# sch.net
KiCad netlist of a schematic drawn in Altium Designer
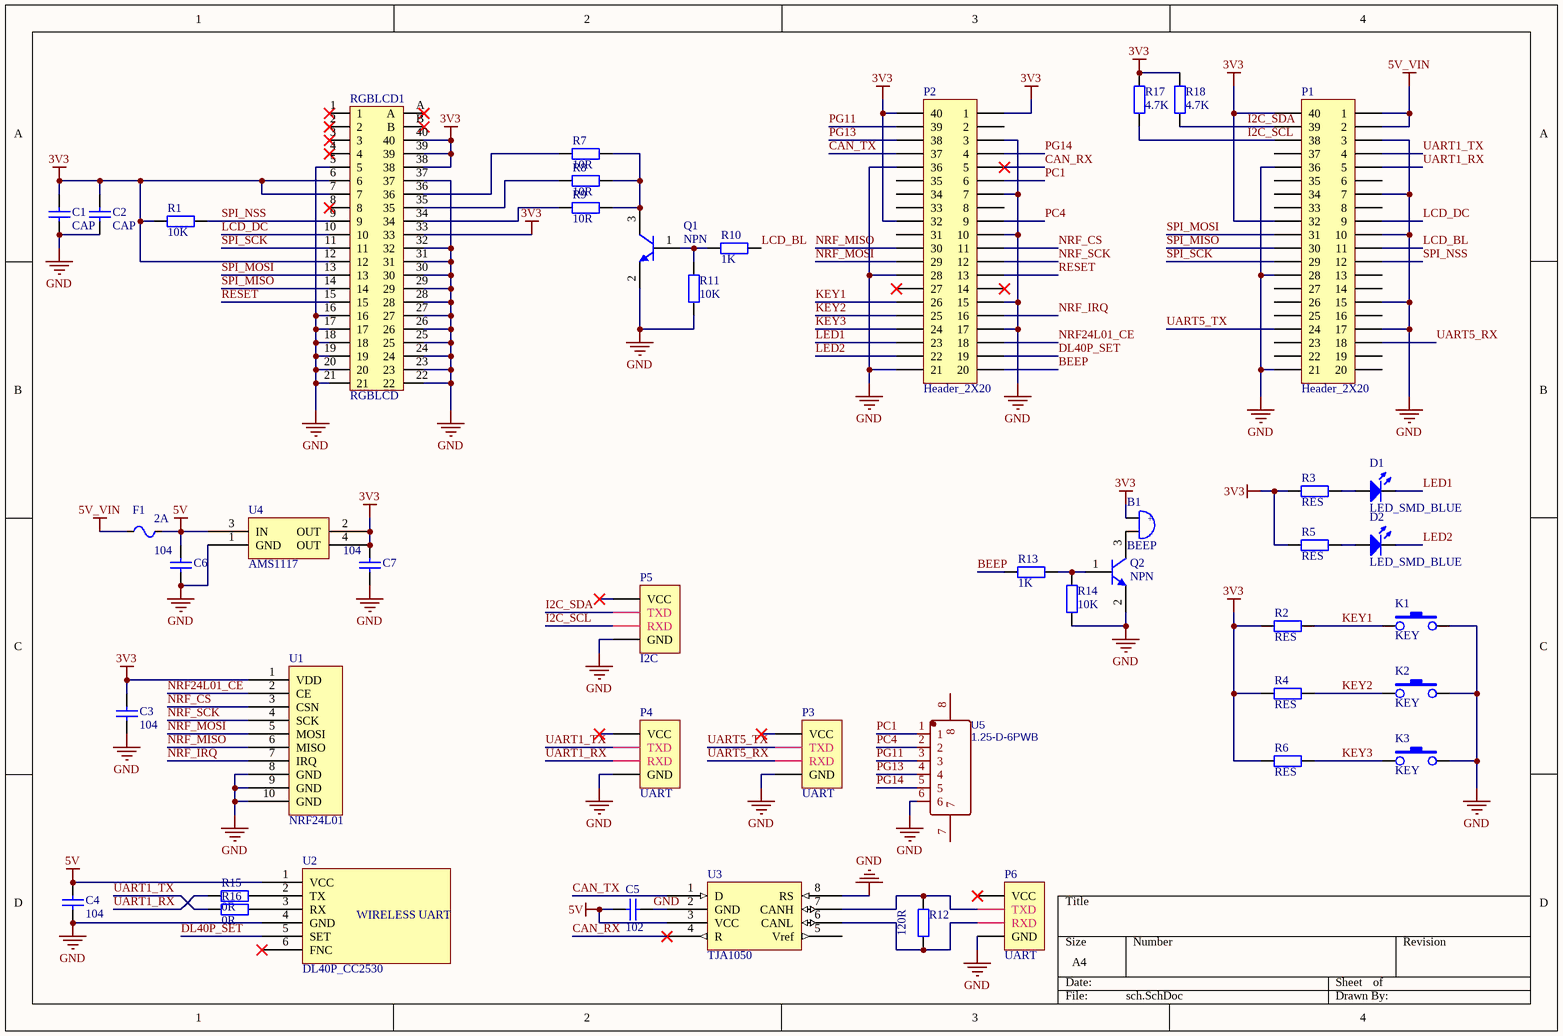
[diagram p0: sch.SchDoc]

(export (version "E")
  (design (tool "Eeschema 10.0.6"))
  (components
    (comp (ref "B1")
      (value "BEEP")
      (footprint "BEEP 5x9x5.5")
      (description "蜂鸣器")
      (libsource (lib "Miscellaneous Model") (part "BEEP"))
    )
    (comp (ref "C1")
      (value "CAP")
      (footprint "Cap-0603")
      (description "贴片陶瓷电容")
      (libsource (lib "Miscellaneous Base") (part "CAP"))
    )
    (comp (ref "C2")
      (value "CAP")
      (footprint "Cap-0603")
      (description "贴片陶瓷电容")
      (libsource (lib "Miscellaneous Base") (part "CAP"))
    )
    (comp (ref "C3")
      (value "104")
      (footprint "Cap-0603")
      (description "贴片陶瓷电容")
      (libsource (lib "Miscellaneous Base") (part "CAP"))
    )
    (comp (ref "C4")
      (value "104")
      (footprint "Cap-0603")
      (description "贴片陶瓷电容")
      (libsource (lib "Miscellaneous Base") (part "CAP"))
    )
    (comp (ref "C5")
      (value "102")
      (footprint "Cap-0603")
      (description "贴片陶瓷电容")
      (libsource (lib "Miscellaneous Base") (part "CAP"))
    )
    (comp (ref "C6")
      (value "104")
      (footprint "Cap-0603")
      (description "贴片陶瓷电容")
      (libsource (lib "Miscellaneous Base") (part "CAP"))
    )
    (comp (ref "C7")
      (value "104")
      (footprint "Cap-0603")
      (description "贴片陶瓷电容")
      (libsource (lib "Miscellaneous Base") (part "CAP"))
    )
    (comp (ref "D1")
      (value "LED_SMD_BLUE")
      (footprint "LED_0603_B")
      (description "发光二极管")
      (libsource (lib "Miscellaneous Transistor") (part "LED_SMD_BLUE"))
    )
    (comp (ref "D2")
      (value "LED_SMD_BLUE")
      (footprint "LED_0603_B")
      (description "发光二极管")
      (libsource (lib "Miscellaneous Transistor") (part "LED_SMD_BLUE"))
    )
    (comp (ref "F1")
      (value "2A")
      (footprint "FU 1206")
      (description "贴片保险丝")
      (fields (field (name "版权归属") "源创客"))
      (libsource (lib "IMX6UL_ALPHA(底板)_V2.0") (part "FU"))
    )
    (comp (ref "K1")
      (value "KEY")
      (footprint "SW-SMD-2X4")
      (libsource (lib "Miscellaneous Switch") (part "KEY"))
    )
    (comp (ref "K2")
      (value "KEY")
      (footprint "SW-SMD-2X4")
      (libsource (lib "Miscellaneous Switch") (part "KEY"))
    )
    (comp (ref "K3")
      (value "KEY")
      (footprint "SW-SMD-2X4")
      (libsource (lib "Miscellaneous Switch") (part "KEY"))
    )
    (comp (ref "P1")
      (value "Header_2X20")
      (footprint "Header 2.54_2X20")
      (libsource (lib "Miscellaneous Header") (part "Header_2X20"))
    )
    (comp (ref "P2")
      (value "Header_2X20")
      (footprint "Header 2.54_2X20")
      (libsource (lib "Miscellaneous Header") (part "Header_2X20"))
    )
    (comp (ref "P3")
      (value "UART")
      (footprint "SMT1.25_4P-90")
      (fields (field (name "PUBLISHER") "Altium Limited"))
      (libsource (lib "我的原理图库") (part "UART port"))
    )
    (comp (ref "P4")
      (value "UART")
      (footprint "SMT1.25_4P-90")
      (fields (field (name "PUBLISHER") "Altium Limited"))
      (libsource (lib "我的原理图库") (part "UART port"))
    )
    (comp (ref "P5")
      (value "I2C")
      (footprint "SMT1.25_4P-90")
      (fields (field (name "PUBLISHER") "Altium Limited"))
      (libsource (lib "我的原理图库") (part "UART port"))
    )
    (comp (ref "P6")
      (value "UART")
      (footprint "SMT1.25_4P-90")
      (fields (field (name "PUBLISHER") "Altium Limited"))
      (libsource (lib "我的原理图库") (part "UART port"))
    )
    (comp (ref "Q1")
      (value "NPN")
      (footprint "SOT23-3")
      (description "贴片三极管")
      (fields (field (name "PUBLISHER") "Altium Limited"))
      (libsource (lib "Miscellaneous Transistor") (part "NPN1"))
    )
    (comp (ref "Q2")
      (value "NPN")
      (footprint "SOT23-3")
      (description "贴片三极管")
      (fields (field (name "PUBLISHER") "Altium Limited"))
      (libsource (lib "Miscellaneous Transistor") (part "NPN1"))
    )
    (comp (ref "R1")
      (value "10K")
      (footprint "Res-0603")
      (description "贴片电阻")
      (libsource (lib "") (part "RES_2"))
    )
    (comp (ref "R2")
      (value "RES")
      (footprint "Res-0603")
      (description "贴片电阻")
      (libsource (lib "") (part "RES_2"))
    )
    (comp (ref "R3")
      (value "RES")
      (footprint "Res-0603")
      (description "贴片电阻")
      (libsource (lib "") (part "RES_2"))
    )
    (comp (ref "R4")
      (value "RES")
      (footprint "Res-0603")
      (description "贴片电阻")
      (libsource (lib "") (part "RES_2"))
    )
    (comp (ref "R5")
      (value "RES")
      (footprint "Res-0603")
      (description "贴片电阻")
      (libsource (lib "") (part "RES_2"))
    )
    (comp (ref "R6")
      (value "RES")
      (footprint "Res-0603")
      (description "贴片电阻")
      (libsource (lib "") (part "RES_2"))
    )
    (comp (ref "R7")
      (value "10R")
      (footprint "Res-0603")
      (description "贴片电阻")
      (libsource (lib "") (part "RES_1"))
    )
    (comp (ref "R8")
      (value "10R")
      (footprint "Res-0603")
      (description "贴片电阻")
      (libsource (lib "") (part "RES_1"))
    )
    (comp (ref "R9")
      (value "10R")
      (footprint "Res-0603")
      (description "贴片电阻")
      (libsource (lib "") (part "RES_1"))
    )
    (comp (ref "R10")
      (value "1K")
      (footprint "Res-0603")
      (description "贴片电阻")
      (libsource (lib "") (part "RES_1"))
    )
    (comp (ref "R11")
      (value "10K")
      (footprint "Res-0603")
      (description "贴片电阻")
      (libsource (lib "") (part "RES_2"))
    )
    (comp (ref "R12")
      (value "120R")
      (footprint "Res-0603")
      (description "贴片电阻")
      (libsource (lib "Miscellaneous Base") (part "RES"))
    )
    (comp (ref "R13")
      (value "1K")
      (footprint "Res-0603")
      (description "贴片电阻")
      (libsource (lib "") (part "RES_1"))
    )
    (comp (ref "R14")
      (value "10K")
      (footprint "Res-0603")
      (description "贴片电阻")
      (libsource (lib "") (part "RES_2"))
    )
    (comp (ref "R15")
      (value "0R")
      (footprint "Res-0603")
      (description "贴片电阻")
      (libsource (lib "") (part "RES_3"))
    )
    (comp (ref "R16")
      (value "0R")
      (footprint "Res-0603")
      (description "贴片电阻")
      (libsource (lib "") (part "RES_3"))
    )
    (comp (ref "R17")
      (value "4.7K")
      (footprint "Res-0603")
      (description "贴片电阻")
      (libsource (lib "Miscellaneous Base") (part "RES"))
    )
    (comp (ref "R18")
      (value "4.7K")
      (footprint "Res-0603")
      (description "贴片电阻")
      (libsource (lib "Miscellaneous Base") (part "RES"))
    )
    (comp (ref "RGBLCD1")
      (value "RGBLCD")
      (footprint "FPC0.5-TOP40P")
      (description "FPC-40P-0.5mm")
      (libsource (lib "IMX6UL_ALPHA(底板)_V2.0") (part "FPC-40"))
    )
    (comp (ref "U1")
      (value "NRF24L01")
      (footprint "PE01-ML01SP4")
      (libsource (lib "OUR_LIB") (part "NRF24L01"))
    )
    (comp (ref "U2")
      (value "DL40P_CC2530")
      (footprint "DL43P_CC2530")
      (libsource (lib "OUR_LIB") (part "DL40P_CC2530"))
    )
    (comp (ref "U3")
      (value "TJA1050")
      (footprint "SOP8_N")
      (libsource (lib "IMX6UL_ALPHA(底板)_V2.0") (part "SN65HVD230D"))
    )
    (comp (ref "U4")
      (value "AMS1117")
      (footprint "AMS1117")
      (libsource (lib "Miscellaneous PMIC") (part "AMS1117"))
    )
    (comp (ref "U5")
      (value "1.25-D-6PWB")
      (footprint "SMT1.25_6P-90")
      (fields (field (name "BOM_SUPPLIER PART") "C35040") (field (name "CONTRIBUTOR") "LCSC"))
      (libsource (lib "我的原理图库") (part "1.25-D-6PWB"))
    )
  )
  (nets
    (net (code "1") (name "/BEEP") (class "Default")
      (node (ref "P2") (pin "20") (pinfunction "20_20") (pintype "power_in"))
      (node (ref "R13") (pin "2") (pinfunction "2_2") (pintype "passive"))
    )
    (net (code "2") (name "/CAN_RX") (class "Default")
      (node (ref "P2") (pin "5") (pinfunction "5_5") (pintype "power_in"))
      (node (ref "U3") (pin "4") (pinfunction "R_4") (pintype "output"))
    )
    (net (code "3") (name "/CAN_TX") (class "Default")
      (node (ref "P2") (pin "37") (pinfunction "37_37") (pintype "power_in"))
      (node (ref "U3") (pin "1") (pinfunction "D_1") (pintype "input"))
    )
    (net (code "4") (name "/DL40P_SET") (class "Default")
      (node (ref "P2") (pin "19") (pinfunction "19_19") (pintype "power_in"))
      (node (ref "U2") (pin "5") (pinfunction "SET_5") (pintype "passive"))
    )
    (net (code "5") (name "/I2C_SCL") (class "Default")
      (node (ref "P1") (pin "38") (pinfunction "38_38") (pintype "power_in"))
      (node (ref "P5") (pin "3") (pinfunction "RXD_3") (pintype "passive"))
      (node (ref "R17") (pin "1") (pinfunction "1_1") (pintype "passive"))
    )
    (net (code "6") (name "/I2C_SDA") (class "Default")
      (node (ref "P1") (pin "39") (pinfunction "39_39") (pintype "power_in"))
      (node (ref "P5") (pin "2") (pinfunction "TXD_2") (pintype "passive"))
      (node (ref "R18") (pin "1") (pinfunction "1_1") (pintype "passive"))
    )
    (net (code "7") (name "/KEY1") (class "Default")
      (node (ref "K1") (pin "1") (pinfunction "1_1") (pintype "passive"))
      (node (ref "P2") (pin "26") (pinfunction "26_26") (pintype "power_in"))
      (node (ref "R2") (pin "2") (pinfunction "2_2") (pintype "passive"))
    )
    (net (code "8") (name "/KEY2") (class "Default")
      (node (ref "K2") (pin "1") (pinfunction "1_1") (pintype "passive"))
      (node (ref "P2") (pin "25") (pinfunction "25_25") (pintype "power_in"))
      (node (ref "R4") (pin "2") (pinfunction "2_2") (pintype "passive"))
    )
    (net (code "9") (name "/KEY3") (class "Default")
      (node (ref "K3") (pin "1") (pinfunction "1_1") (pintype "passive"))
      (node (ref "P2") (pin "24") (pinfunction "24_24") (pintype "power_in"))
      (node (ref "R6") (pin "2") (pinfunction "2_2") (pintype "passive"))
    )
    (net (code "10") (name "/LCD_BL") (class "Default")
      (node (ref "P1") (pin "11") (pinfunction "11_11") (pintype "power_in"))
      (node (ref "R10") (pin "1") (pinfunction "1_1") (pintype "passive"))
    )
    (net (code "11") (name "/LCD_DC") (class "Default")
      (node (ref "P1") (pin "9") (pinfunction "9_9") (pintype "power_in"))
      (node (ref "RGBLCD1") (pin "10") (pinfunction "10_10") (pintype "passive"))
    )
    (net (code "12") (name "/LED1") (class "Default")
      (node (ref "D1") (pin "2") (pinfunction "K_2") (pintype "passive"))
      (node (ref "P2") (pin "23") (pinfunction "23_23") (pintype "power_in"))
    )
    (net (code "13") (name "/LED2") (class "Default")
      (node (ref "D2") (pin "2") (pinfunction "K_2") (pintype "passive"))
      (node (ref "P2") (pin "22") (pinfunction "22_22") (pintype "power_in"))
    )
    (net (code "14") (name "/NRF24L01_CE") (class "Default")
      (node (ref "P2") (pin "18") (pinfunction "18_18") (pintype "power_in"))
      (node (ref "U1") (pin "2") (pinfunction "CE_2") (pintype "passive"))
    )
    (net (code "15") (name "/NRF_CS") (class "Default")
      (node (ref "P2") (pin "11") (pinfunction "11_11") (pintype "power_in"))
      (node (ref "U1") (pin "3") (pinfunction "CSN_3") (pintype "passive"))
    )
    (net (code "16") (name "/NRF_IRQ") (class "Default")
      (node (ref "P2") (pin "16") (pinfunction "16_16") (pintype "power_in"))
      (node (ref "U1") (pin "7") (pinfunction "IRQ_7") (pintype "passive"))
    )
    (net (code "17") (name "/NRF_MISO") (class "Default")
      (node (ref "P2") (pin "30") (pinfunction "30_30") (pintype "power_in"))
      (node (ref "U1") (pin "6") (pinfunction "MISO_6") (pintype "passive"))
    )
    (net (code "18") (name "/NRF_MOSI") (class "Default")
      (node (ref "P2") (pin "29") (pinfunction "29_29") (pintype "power_in"))
      (node (ref "U1") (pin "5") (pinfunction "MOSI_5") (pintype "passive"))
    )
    (net (code "19") (name "/NRF_SCK") (class "Default")
      (node (ref "P2") (pin "12") (pinfunction "12_12") (pintype "power_in"))
      (node (ref "U1") (pin "4") (pinfunction "SCK_4") (pintype "passive"))
    )
    (net (code "20") (name "/PC1") (class "Default")
      (node (ref "P2") (pin "6") (pinfunction "6_6") (pintype "power_in"))
      (node (ref "U5") (pin "1") (pinfunction "1_1") (pintype "passive"))
    )
    (net (code "21") (name "/PC4") (class "Default")
      (node (ref "P2") (pin "9") (pinfunction "9_9") (pintype "power_in"))
      (node (ref "U5") (pin "2") (pinfunction "2_2") (pintype "passive"))
    )
    (net (code "22") (name "/PG11") (class "Default")
      (node (ref "P2") (pin "39") (pinfunction "39_39") (pintype "power_in"))
      (node (ref "U5") (pin "3") (pinfunction "3_3") (pintype "passive"))
    )
    (net (code "23") (name "/PG13") (class "Default")
      (node (ref "P2") (pin "38") (pinfunction "38_38") (pintype "power_in"))
      (node (ref "U5") (pin "4") (pinfunction "4_4") (pintype "passive"))
    )
    (net (code "24") (name "/PG14") (class "Default")
      (node (ref "P2") (pin "4") (pinfunction "4_4") (pintype "power_in"))
      (node (ref "U5") (pin "5") (pinfunction "5_5") (pintype "passive"))
    )
    (net (code "25") (name "/RESET") (class "Default")
      (node (ref "P2") (pin "13") (pinfunction "13_13") (pintype "power_in"))
      (node (ref "RGBLCD1") (pin "15") (pinfunction "15_15") (pintype "passive"))
    )
    (net (code "26") (name "/SPI_MISO") (class "Default")
      (node (ref "P1") (pin "30") (pinfunction "30_30") (pintype "power_in"))
      (node (ref "RGBLCD1") (pin "14") (pinfunction "14_14") (pintype "passive"))
    )
    (net (code "27") (name "/SPI_MOSI") (class "Default")
      (node (ref "P1") (pin "31") (pinfunction "31_31") (pintype "power_in"))
      (node (ref "RGBLCD1") (pin "13") (pinfunction "13_13") (pintype "passive"))
    )
    (net (code "28") (name "/SPI_NSS") (class "Default")
      (node (ref "P1") (pin "12") (pinfunction "12_12") (pintype "power_in"))
      (node (ref "R1") (pin "2") (pinfunction "2_2") (pintype "passive"))
      (node (ref "RGBLCD1") (pin "9") (pinfunction "9_9") (pintype "passive"))
    )
    (net (code "29") (name "/SPI_SCK") (class "Default")
      (node (ref "P1") (pin "29") (pinfunction "29_29") (pintype "power_in"))
      (node (ref "RGBLCD1") (pin "11") (pinfunction "11_11") (pintype "passive"))
    )
    (net (code "30") (name "/UART1_RX") (class "Default")
      (node (ref "P1") (pin "5") (pinfunction "5_5") (pintype "power_in"))
      (node (ref "P4") (pin "3") (pinfunction "RXD_3") (pintype "passive"))
      (node (ref "R15") (pin "2") (pinfunction "2_2") (pintype "passive"))
    )
    (net (code "31") (name "/UART1_TX") (class "Default")
      (node (ref "P1") (pin "4") (pinfunction "4_4") (pintype "power_in"))
      (node (ref "P4") (pin "2") (pinfunction "TXD_2") (pintype "passive"))
      (node (ref "R16") (pin "2") (pinfunction "2_2") (pintype "passive"))
    )
    (net (code "32") (name "/UART5_RX") (class "Default")
      (node (ref "P1") (pin "18") (pinfunction "18_18") (pintype "power_in"))
      (node (ref "P3") (pin "3") (pinfunction "RXD_3") (pintype "passive"))
    )
    (net (code "33") (name "/UART5_TX") (class "Default")
      (node (ref "P1") (pin "24") (pinfunction "24_24") (pintype "power_in"))
      (node (ref "P3") (pin "2") (pinfunction "TXD_2") (pintype "passive"))
    )
    (net (code "34") (name "3V3") (class "Default")
      (node (ref "B1") (pin "1") (pinfunction "1_1") (pintype "passive"))
      (node (ref "C1") (pin "2") (pinfunction "2_2") (pintype "passive"))
      (node (ref "C2") (pin "2") (pinfunction "2_2") (pintype "passive"))
      (node (ref "C3") (pin "2") (pinfunction "2_2") (pintype "passive"))
      (node (ref "C7") (pin "1") (pinfunction "1_1") (pintype "passive"))
      (node (ref "P1") (pin "32") (pinfunction "32_32") (pintype "power_in"))
      (node (ref "P1") (pin "40") (pinfunction "40_40") (pintype "power_in"))
      (node (ref "P2") (pin "1") (pinfunction "1_1") (pintype "power_in"))
      (node (ref "P2") (pin "32") (pinfunction "32_32") (pintype "power_in"))
      (node (ref "P2") (pin "40") (pinfunction "40_40") (pintype "power_in"))
      (node (ref "R1") (pin "1") (pinfunction "1_1") (pintype "passive"))
      (node (ref "R17") (pin "2") (pinfunction "2_2") (pintype "passive"))
      (node (ref "R18") (pin "2") (pinfunction "2_2") (pintype "passive"))
      (node (ref "R2") (pin "1") (pinfunction "1_1") (pintype "passive"))
      (node (ref "R3") (pin "1") (pinfunction "1_1") (pintype "passive"))
      (node (ref "R4") (pin "1") (pinfunction "1_1") (pintype "passive"))
      (node (ref "R5") (pin "1") (pinfunction "1_1") (pintype "passive"))
      (node (ref "R6") (pin "1") (pinfunction "1_1") (pintype "passive"))
      (node (ref "RGBLCD1") (pin "12") (pinfunction "12_12") (pintype "passive"))
      (node (ref "RGBLCD1") (pin "33") (pinfunction "33_33") (pintype "passive"))
      (node (ref "RGBLCD1") (pin "38") (pinfunction "38_38") (pintype "passive"))
      (node (ref "RGBLCD1") (pin "39") (pinfunction "39_39") (pintype "passive"))
      (node (ref "RGBLCD1") (pin "40") (pinfunction "40_40") (pintype "passive"))
      (node (ref "RGBLCD1") (pin "6") (pinfunction "6_6") (pintype "passive"))
      (node (ref "RGBLCD1") (pin "7") (pinfunction "7_7") (pintype "passive"))
      (node (ref "U1") (pin "1") (pinfunction "VDD_1") (pintype "passive"))
      (node (ref "U4") (pin "2") (pinfunction "OUT_2") (pintype "passive"))
      (node (ref "U4") (pin "4") (pinfunction "OUT_4") (pintype "passive"))
    )
    (net (code "35") (name "5V") (class "Default")
      (node (ref "C4") (pin "2") (pinfunction "2_2") (pintype "passive"))
      (node (ref "C5") (pin "1") (pinfunction "1_1") (pintype "passive"))
      (node (ref "C6") (pin "1") (pinfunction "1_1") (pintype "passive"))
      (node (ref "F1") (pin "2") (pinfunction "2_2") (pintype "passive"))
      (node (ref "U2") (pin "1") (pinfunction "VCC_1") (pintype "passive"))
      (node (ref "U3") (pin "3") (pinfunction "VCC_3") (pintype "power_in"))
      (node (ref "U4") (pin "3") (pinfunction "IN_3") (pintype "passive"))
    )
    (net (code "36") (name "5V_VIN") (class "Default")
      (node (ref "F1") (pin "1") (pinfunction "1_1") (pintype "passive"))
      (node (ref "P1") (pin "1") (pinfunction "1_1") (pintype "power_in"))
      (node (ref "P1") (pin "2") (pinfunction "2_2") (pintype "power_in"))
    )
    (net (code "37") (name "GND") (class "Default")
      (node (ref "C1") (pin "1") (pinfunction "1_1") (pintype "passive"))
      (node (ref "C2") (pin "1") (pinfunction "1_1") (pintype "passive"))
      (node (ref "C3") (pin "1") (pinfunction "1_1") (pintype "passive"))
      (node (ref "C4") (pin "1") (pinfunction "1_1") (pintype "passive"))
      (node (ref "C5") (pin "2") (pinfunction "2_2") (pintype "passive"))
      (node (ref "C6") (pin "2") (pinfunction "2_2") (pintype "passive"))
      (node (ref "C7") (pin "2") (pinfunction "2_2") (pintype "passive"))
      (node (ref "K1") (pin "3") (pinfunction "3_3") (pintype "passive"))
      (node (ref "K2") (pin "3") (pinfunction "3_3") (pintype "passive"))
      (node (ref "K3") (pin "3") (pinfunction "3_3") (pintype "passive"))
      (node (ref "P1") (pin "10") (pinfunction "10_10") (pintype "power_in"))
      (node (ref "P1") (pin "15") (pinfunction "15_15") (pintype "power_in"))
      (node (ref "P1") (pin "17") (pinfunction "17_17") (pintype "power_in"))
      (node (ref "P1") (pin "21") (pinfunction "21_21") (pintype "power_in"))
      (node (ref "P1") (pin "28") (pinfunction "28_28") (pintype "power_in"))
      (node (ref "P1") (pin "3") (pinfunction "3_3") (pintype "power_in"))
      (node (ref "P1") (pin "36") (pinfunction "36_36") (pintype "power_in"))
      (node (ref "P1") (pin "7") (pinfunction "7_7") (pintype "power_in"))
      (node (ref "P2") (pin "10") (pinfunction "10_10") (pintype "power_in"))
      (node (ref "P2") (pin "15") (pinfunction "15_15") (pintype "power_in"))
      (node (ref "P2") (pin "17") (pinfunction "17_17") (pintype "power_in"))
      (node (ref "P2") (pin "21") (pinfunction "21_21") (pintype "power_in"))
      (node (ref "P2") (pin "28") (pinfunction "28_28") (pintype "power_in"))
      (node (ref "P2") (pin "3") (pinfunction "3_3") (pintype "power_in"))
      (node (ref "P2") (pin "36") (pinfunction "36_36") (pintype "power_in"))
      (node (ref "P2") (pin "7") (pinfunction "7_7") (pintype "power_in"))
      (node (ref "P3") (pin "4") (pinfunction "GND_4") (pintype "passive"))
      (node (ref "P4") (pin "4") (pinfunction "GND_4") (pintype "passive"))
      (node (ref "P5") (pin "4") (pinfunction "GND_4") (pintype "passive"))
      (node (ref "P6") (pin "4") (pinfunction "GND_4") (pintype "passive"))
      (node (ref "Q1") (pin "2") (pinfunction "E_2") (pintype "passive"))
      (node (ref "Q2") (pin "2") (pinfunction "E_2") (pintype "passive"))
      (node (ref "R11") (pin "1") (pinfunction "1_1") (pintype "passive"))
      (node (ref "R14") (pin "1") (pinfunction "1_1") (pintype "passive"))
      (node (ref "RGBLCD1") (pin "16") (pinfunction "16_16") (pintype "passive"))
      (node (ref "RGBLCD1") (pin "17") (pinfunction "17_17") (pintype "passive"))
      (node (ref "RGBLCD1") (pin "18") (pinfunction "18_18") (pintype "passive"))
      (node (ref "RGBLCD1") (pin "19") (pinfunction "19_19") (pintype "passive"))
      (node (ref "RGBLCD1") (pin "20") (pinfunction "20_20") (pintype "passive"))
      (node (ref "RGBLCD1") (pin "21") (pinfunction "21_21") (pintype "passive"))
      (node (ref "RGBLCD1") (pin "22") (pinfunction "22_22") (pintype "passive"))
      (node (ref "RGBLCD1") (pin "23") (pinfunction "23_23") (pintype "passive"))
      (node (ref "RGBLCD1") (pin "24") (pinfunction "24_24") (pintype "passive"))
      (node (ref "RGBLCD1") (pin "25") (pinfunction "25_25") (pintype "passive"))
      (node (ref "RGBLCD1") (pin "26") (pinfunction "26_26") (pintype "passive"))
      (node (ref "RGBLCD1") (pin "27") (pinfunction "27_27") (pintype "passive"))
      (node (ref "RGBLCD1") (pin "28") (pinfunction "28_28") (pintype "passive"))
      (node (ref "RGBLCD1") (pin "29") (pinfunction "29_29") (pintype "passive"))
      (node (ref "RGBLCD1") (pin "30") (pinfunction "30_30") (pintype "passive"))
      (node (ref "RGBLCD1") (pin "31") (pinfunction "31_31") (pintype "passive"))
      (node (ref "RGBLCD1") (pin "32") (pinfunction "32_32") (pintype "passive"))
      (node (ref "RGBLCD1") (pin "37") (pinfunction "37_37") (pintype "passive"))
      (node (ref "RGBLCD1") (pin "5") (pinfunction "5_5") (pintype "passive"))
      (node (ref "U1") (pin "10") (pinfunction "GND_10") (pintype "passive"))
      (node (ref "U1") (pin "8") (pinfunction "GND_8") (pintype "passive"))
      (node (ref "U1") (pin "9") (pinfunction "GND_9") (pintype "passive"))
      (node (ref "U2") (pin "4") (pinfunction "GND_4") (pintype "passive"))
      (node (ref "U3") (pin "2") (pinfunction "GND_2") (pintype "power_in"))
      (node (ref "U3") (pin "8") (pinfunction "RS_8") (pintype "input"))
      (node (ref "U4") (pin "1") (pinfunction "GND_1") (pintype "passive"))
      (node (ref "U5") (pin "6") (pinfunction "6_6") (pintype "passive"))
    )
    (net (code "38") (name "Net-(D1-A)") (class "Default")
      (node (ref "D1") (pin "1") (pinfunction "A_1") (pintype "passive"))
      (node (ref "R3") (pin "2") (pinfunction "2_2") (pintype "passive"))
    )
    (net (code "39") (name "Net-(D2-A)") (class "Default")
      (node (ref "D2") (pin "1") (pinfunction "A_1") (pintype "passive"))
      (node (ref "R5") (pin "2") (pinfunction "2_2") (pintype "passive"))
    )
    (net (code "40") (name "Net-(P6-RXD)") (class "Default")
      (node (ref "P6") (pin "3") (pinfunction "RXD_3") (pintype "passive"))
      (node (ref "R12") (pin "1") (pinfunction "1_1") (pintype "passive"))
      (node (ref "U3") (pin "6") (pinfunction "CANL_6") (pintype "bidirectional"))
    )
    (net (code "41") (name "Net-(P6-TXD)") (class "Default")
      (node (ref "P6") (pin "2") (pinfunction "TXD_2") (pintype "passive"))
      (node (ref "R12") (pin "2") (pinfunction "2_2") (pintype "passive"))
      (node (ref "U3") (pin "7") (pinfunction "CANH_7") (pintype "bidirectional"))
    )
    (net (code "42") (name "Net-(Q1-B)") (class "Default")
      (node (ref "Q1") (pin "1") (pinfunction "B_1") (pintype "passive"))
      (node (ref "R10") (pin "2") (pinfunction "2_2") (pintype "passive"))
      (node (ref "R11") (pin "2") (pinfunction "2_2") (pintype "passive"))
    )
    (net (code "43") (name "Net-(Q1-C)") (class "Default")
      (node (ref "Q1") (pin "3") (pinfunction "C_3") (pintype "passive"))
      (node (ref "R7") (pin "1") (pinfunction "1_1") (pintype "passive"))
      (node (ref "R8") (pin "1") (pinfunction "1_1") (pintype "passive"))
      (node (ref "R9") (pin "1") (pinfunction "1_1") (pintype "passive"))
    )
    (net (code "44") (name "Net-(Q2-B)") (class "Default")
      (node (ref "Q2") (pin "1") (pinfunction "B_1") (pintype "passive"))
      (node (ref "R13") (pin "1") (pinfunction "1_1") (pintype "passive"))
      (node (ref "R14") (pin "2") (pinfunction "2_2") (pintype "passive"))
    )
    (net (code "45") (name "Net-(Q2-C)") (class "Default")
      (node (ref "B1") (pin "2") (pinfunction "2_2") (pintype "passive"))
      (node (ref "Q2") (pin "3") (pinfunction "C_3") (pintype "passive"))
    )
    (net (code "46") (name "Net-(R7-Pad2)") (class "Default")
      (node (ref "R7") (pin "2") (pinfunction "2_2") (pintype "passive"))
      (node (ref "RGBLCD1") (pin "36") (pinfunction "36_36") (pintype "passive"))
    )
    (net (code "47") (name "Net-(R8-Pad2)") (class "Default")
      (node (ref "R8") (pin "2") (pinfunction "2_2") (pintype "passive"))
      (node (ref "RGBLCD1") (pin "35") (pinfunction "35_35") (pintype "passive"))
    )
    (net (code "48") (name "Net-(R9-Pad2)") (class "Default")
      (node (ref "R9") (pin "2") (pinfunction "2_2") (pintype "passive"))
      (node (ref "RGBLCD1") (pin "34") (pinfunction "34_34") (pintype "passive"))
    )
    (net (code "49") (name "Net-(U2-RX)") (class "Default")
      (node (ref "R16") (pin "1") (pinfunction "1_1") (pintype "passive"))
      (node (ref "U2") (pin "3") (pinfunction "RX_3") (pintype "passive"))
    )
    (net (code "50") (name "Net-(U2-TX)") (class "Default")
      (node (ref "R15") (pin "1") (pinfunction "1_1") (pintype "passive"))
      (node (ref "U2") (pin "2") (pinfunction "TX_2") (pintype "passive"))
    )
    (net (code "51") (name "unconnected-(P1-Pad6)") (class "Default")
      (node (ref "P1") (pin "6") (pinfunction "6_6") (pintype "power_in"))
    )
    (net (code "52") (name "unconnected-(P1-Pad8)") (class "Default")
      (node (ref "P1") (pin "8") (pinfunction "8_8") (pintype "power_in"))
    )
    (net (code "53") (name "unconnected-(P1-Pad13)") (class "Default")
      (node (ref "P1") (pin "13") (pinfunction "13_13") (pintype "power_in"))
    )
    (net (code "54") (name "unconnected-(P1-Pad14)") (class "Default")
      (node (ref "P1") (pin "14") (pinfunction "14_14") (pintype "power_in"))
    )
    (net (code "55") (name "unconnected-(P1-Pad16)") (class "Default")
      (node (ref "P1") (pin "16") (pinfunction "16_16") (pintype "power_in"))
    )
    (net (code "56") (name "unconnected-(P1-Pad19)") (class "Default")
      (node (ref "P1") (pin "19") (pinfunction "19_19") (pintype "power_in"))
    )
    (net (code "57") (name "unconnected-(P1-Pad20)") (class "Default")
      (node (ref "P1") (pin "20") (pinfunction "20_20") (pintype "power_in"))
    )
    (net (code "58") (name "unconnected-(P1-Pad22)") (class "Default")
      (node (ref "P1") (pin "22") (pinfunction "22_22") (pintype "power_in"))
    )
    (net (code "59") (name "unconnected-(P1-Pad23)") (class "Default")
      (node (ref "P1") (pin "23") (pinfunction "23_23") (pintype "power_in"))
    )
    (net (code "60") (name "unconnected-(P1-Pad25)") (class "Default")
      (node (ref "P1") (pin "25") (pinfunction "25_25") (pintype "power_in"))
    )
    (net (code "61") (name "unconnected-(P1-Pad26)") (class "Default")
      (node (ref "P1") (pin "26") (pinfunction "26_26") (pintype "power_in"))
    )
    (net (code "62") (name "unconnected-(P1-Pad27)") (class "Default")
      (node (ref "P1") (pin "27") (pinfunction "27_27") (pintype "power_in"))
    )
    (net (code "63") (name "unconnected-(P1-Pad33)") (class "Default")
      (node (ref "P1") (pin "33") (pinfunction "33_33") (pintype "power_in"))
    )
    (net (code "64") (name "unconnected-(P1-Pad34)") (class "Default")
      (node (ref "P1") (pin "34") (pinfunction "34_34") (pintype "power_in"))
    )
    (net (code "65") (name "unconnected-(P1-Pad35)") (class "Default")
      (node (ref "P1") (pin "35") (pinfunction "35_35") (pintype "power_in"))
    )
    (net (code "66") (name "unconnected-(P1-Pad37)") (class "Default")
      (node (ref "P1") (pin "37") (pinfunction "37_37") (pintype "power_in"))
    )
    (net (code "67") (name "unconnected-(P2-Pad2)") (class "Default")
      (node (ref "P2") (pin "2") (pinfunction "2_2") (pintype "power_in"))
    )
    (net (code "68") (name "unconnected-(P2-Pad8)") (class "Default")
      (node (ref "P2") (pin "8") (pinfunction "8_8") (pintype "power_in"))
    )
    (net (code "69") (name "unconnected-(P2-Pad14)") (class "Default")
      (node (ref "P2") (pin "14") (pinfunction "14_14") (pintype "power_in+no_connect"))
    )
    (net (code "70") (name "unconnected-(P2-Pad27)") (class "Default")
      (node (ref "P2") (pin "27") (pinfunction "27_27") (pintype "power_in+no_connect"))
    )
    (net (code "71") (name "unconnected-(P2-Pad31)") (class "Default")
      (node (ref "P2") (pin "31") (pinfunction "31_31") (pintype "power_in"))
    )
    (net (code "72") (name "unconnected-(P2-Pad33)") (class "Default")
      (node (ref "P2") (pin "33") (pinfunction "33_33") (pintype "power_in"))
    )
    (net (code "73") (name "unconnected-(P2-Pad34)") (class "Default")
      (node (ref "P2") (pin "34") (pinfunction "34_34") (pintype "power_in"))
    )
    (net (code "74") (name "unconnected-(P2-Pad35)") (class "Default")
      (node (ref "P2") (pin "35") (pinfunction "35_35") (pintype "power_in"))
    )
    (net (code "75") (name "unconnected-(P3-VCC-Pad1)") (class "Default")
      (node (ref "P3") (pin "1") (pinfunction "VCC_1") (pintype "passive+no_connect"))
    )
    (net (code "76") (name "unconnected-(P4-VCC-Pad1)") (class "Default")
      (node (ref "P4") (pin "1") (pinfunction "VCC_1") (pintype "passive+no_connect"))
    )
    (net (code "77") (name "unconnected-(P5-VCC-Pad1)") (class "Default")
      (node (ref "P5") (pin "1") (pinfunction "VCC_1") (pintype "passive+no_connect"))
    )
    (net (code "78") (name "unconnected-(P6-VCC-Pad1)") (class "Default")
      (node (ref "P6") (pin "1") (pinfunction "VCC_1") (pintype "passive+no_connect"))
    )
    (net (code "79") (name "unconnected-(RGBLCD1-Pad1)") (class "Default")
      (node (ref "RGBLCD1") (pin "1") (pinfunction "1_1") (pintype "passive+no_connect"))
    )
    (net (code "80") (name "unconnected-(RGBLCD1-Pad2)") (class "Default")
      (node (ref "RGBLCD1") (pin "2") (pinfunction "2_2") (pintype "passive+no_connect"))
    )
    (net (code "81") (name "unconnected-(RGBLCD1-Pad3)") (class "Default")
      (node (ref "RGBLCD1") (pin "3") (pinfunction "3_3") (pintype "passive+no_connect"))
    )
    (net (code "82") (name "unconnected-(RGBLCD1-Pad4)") (class "Default")
      (node (ref "RGBLCD1") (pin "4") (pinfunction "4_4") (pintype "passive+no_connect"))
    )
    (net (code "83") (name "unconnected-(RGBLCD1-Pad8)") (class "Default")
      (node (ref "RGBLCD1") (pin "8") (pinfunction "8_8") (pintype "passive+no_connect"))
    )
    (net (code "84") (name "unconnected-(RGBLCD1-PadA)") (class "Default")
      (node (ref "RGBLCD1") (pin "A") (pinfunction "A_A") (pintype "passive+no_connect"))
    )
    (net (code "85") (name "unconnected-(RGBLCD1-PadB)") (class "Default")
      (node (ref "RGBLCD1") (pin "B") (pinfunction "B_B") (pintype "passive+no_connect"))
    )
    (net (code "86") (name "unconnected-(U2-FNC-Pad6)") (class "Default")
      (node (ref "U2") (pin "6") (pinfunction "FNC_6") (pintype "passive+no_connect"))
    )
    (net (code "87") (name "unconnected-(U3-Vref-Pad5)") (class "Default")
      (node (ref "U3") (pin "5") (pinfunction "Vref_5") (pintype "output"))
    )
    (net (code "88") (name "unconnected-(U5-Pad7)") (class "Default")
      (node (ref "U5") (pin "7") (pinfunction "7_7") (pintype "passive"))
    )
    (net (code "89") (name "unconnected-(U5-Pad8)") (class "Default")
      (node (ref "U5") (pin "8") (pinfunction "8_8") (pintype "passive"))
    )
  )
)
